# esp-energy-monitor-v2.net
KiCad netlist of a schematic drawn in EAGLE
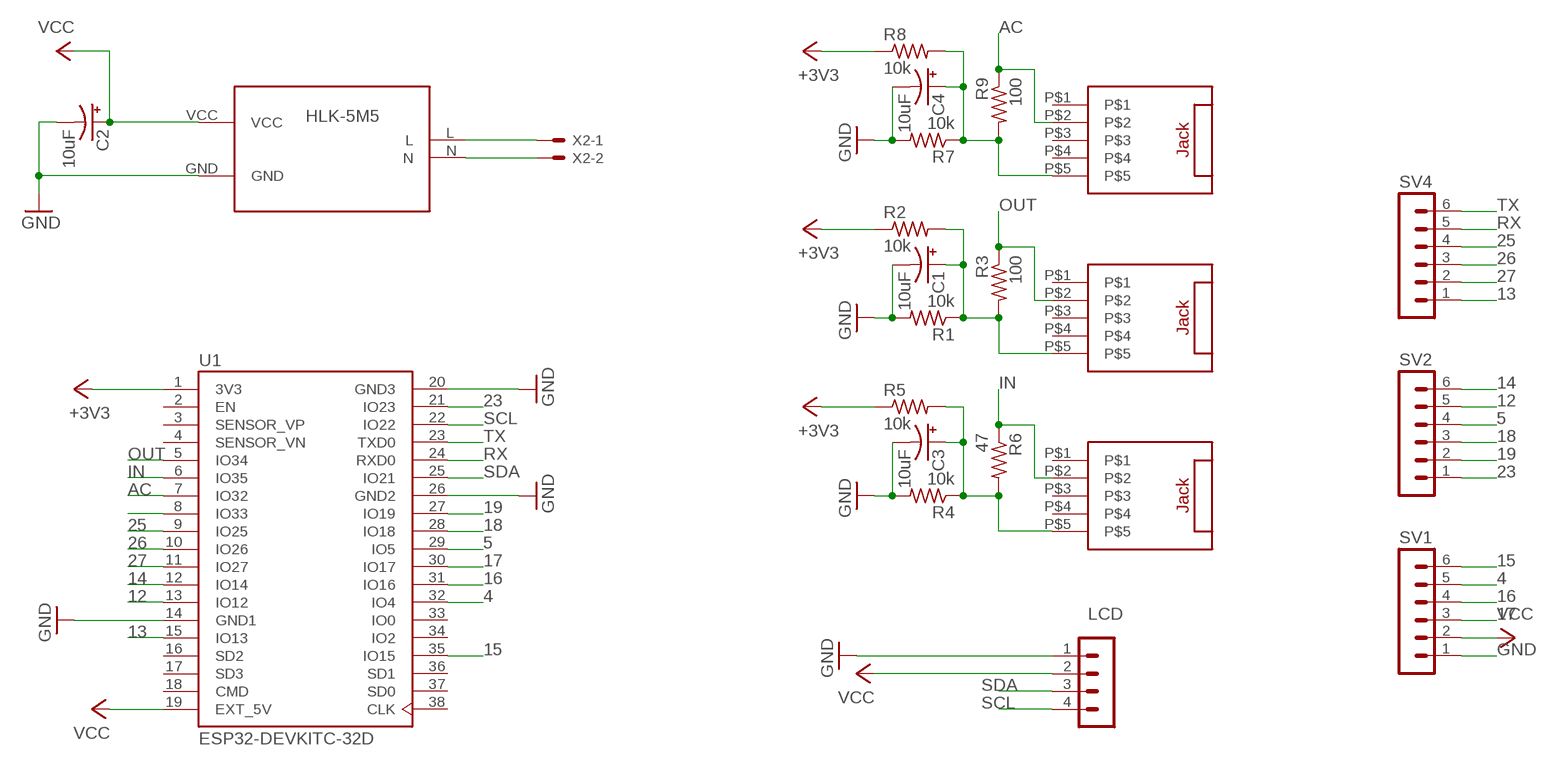
[diagram p0: schematic, sheet 1]

(export (version "E")
  (design (tool "Eeschema 10.0.6"))
  (components
    (comp (ref "ACJACK")
      (value "JACK_5PINS")
      (footprint "eagle-import:JACK_5PINS")
      (libsource (lib "eagle-import") (part "JACK_5PINS"))
    )
    (comp (ref "C1")
      (value "10uF")
      (footprint "eagle-import:B45181A")
      (libsource (lib "eagle-import") (part "CPOL-USB45181A"))
    )
    (comp (ref "C2")
      (value "10uF")
      (footprint "eagle-import:B45181A")
      (libsource (lib "eagle-import") (part "CPOL-USB45181A"))
    )
    (comp (ref "C3")
      (value "10uF")
      (footprint "eagle-import:B45181A")
      (libsource (lib "eagle-import") (part "CPOL-USB45181A"))
    )
    (comp (ref "C4")
      (value "10uF")
      (footprint "eagle-import:B45181A")
      (libsource (lib "eagle-import") (part "CPOL-USB45181A"))
    )
    (comp (ref "HLK-5M5")
      (value "HLK-5M05")
      (footprint "eagle-import:CONV_HLK-5M05")
      (libsource (lib "eagle-import") (part "HLK-5M05"))
    )
    (comp (ref "INJACK")
      (value "JACK_5PINS")
      (footprint "eagle-import:JACK_5PINS")
      (libsource (lib "eagle-import") (part "JACK_5PINS"))
    )
    (comp (ref "OUTJACK")
      (value "JACK_5PINS")
      (footprint "eagle-import:JACK_5PINS")
      (libsource (lib "eagle-import") (part "JACK_5PINS"))
    )
    (comp (ref "R1")
      (value "10k")
      (footprint "eagle-import:0204_7")
      (libsource (lib "eagle-import") (part "R-US_0204/7"))
    )
    (comp (ref "R2")
      (value "10k")
      (footprint "eagle-import:0204_7")
      (libsource (lib "eagle-import") (part "R-US_0204/7"))
    )
    (comp (ref "R3")
      (value "100")
      (footprint "eagle-import:0204_7")
      (libsource (lib "eagle-import") (part "R-US_0204/7"))
    )
    (comp (ref "R4")
      (value "10k")
      (footprint "eagle-import:0204_7")
      (libsource (lib "eagle-import") (part "R-US_0204/7"))
    )
    (comp (ref "R5")
      (value "10k")
      (footprint "eagle-import:0204_7")
      (libsource (lib "eagle-import") (part "R-US_0204/7"))
    )
    (comp (ref "R6")
      (value "47")
      (footprint "eagle-import:0204_7")
      (libsource (lib "eagle-import") (part "R-US_0204/7"))
    )
    (comp (ref "R7")
      (value "10k")
      (footprint "eagle-import:0204_7")
      (libsource (lib "eagle-import") (part "R-US_0204/7"))
    )
    (comp (ref "R8")
      (value "10k")
      (footprint "eagle-import:0204_7")
      (libsource (lib "eagle-import") (part "R-US_0204/7"))
    )
    (comp (ref "R9")
      (value "100")
      (footprint "eagle-import:0204_7")
      (libsource (lib "eagle-import") (part "R-US_0204/7"))
    )
    (comp (ref "SV1")
      (value "MA06-1")
      (footprint "eagle-import:MA06-1")
      (libsource (lib "eagle-import") (part "MA06-1"))
    )
    (comp (ref "SV2")
      (value "MA06-1")
      (footprint "eagle-import:MA06-1")
      (libsource (lib "eagle-import") (part "MA06-1"))
    )
    (comp (ref "SV3")
      (value "MA04-1")
      (footprint "eagle-import:MA04-1")
      (libsource (lib "eagle-import") (part "MA04-1"))
    )
    (comp (ref "SV4")
      (value "MA06-1")
      (footprint "eagle-import:MA06-1")
      (libsource (lib "eagle-import") (part "MA06-1"))
    )
    (comp (ref "U1")
      (value "ESP32-DEVKITC-32D")
      (footprint "eagle-import:MODULE_ESP32-DEVKITC-32D")
      (fields (field (name "MF") "Espressif Systems"))
      (libsource (lib "eagle-import") (part "ESP32-DEVKITC-32D"))
    )
    (comp (ref "X2")
      (value "JST-XH-02-PIN-LONG-PAD")
      (footprint "eagle-import:JST-XH-02-PACKAGE-LONG-PAD")
      (libsource (lib "eagle-import") (part "JST-XH-02-PIN-LONG-PAD"))
    )
  )
  (nets
    (net (code "1") (name "+3V3") (class "Default")
      (node (ref "R2") (pin "1") (pinfunction "1_1") (pintype "passive"))
      (node (ref "R5") (pin "1") (pinfunction "1_1") (pintype "passive"))
      (node (ref "R8") (pin "1") (pinfunction "1_1") (pintype "passive"))
      (node (ref "U1") (pin "1") (pinfunction "3V3_1") (pintype "power_in"))
    )
    (net (code "2") (name "/4") (class "Default")
      (node (ref "SV1") (pin "5") (pinfunction "5_5") (pintype "passive"))
      (node (ref "U1") (pin "32") (pinfunction "IO4_32") (pintype "bidirectional"))
    )
    (net (code "3") (name "/5") (class "Default")
      (node (ref "SV2") (pin "4") (pinfunction "4_4") (pintype "passive"))
      (node (ref "U1") (pin "29") (pinfunction "IO5_29") (pintype "bidirectional"))
    )
    (net (code "4") (name "/12") (class "Default")
      (node (ref "SV2") (pin "5") (pinfunction "5_5") (pintype "passive"))
      (node (ref "U1") (pin "13") (pinfunction "IO12_13") (pintype "bidirectional"))
    )
    (net (code "5") (name "/13") (class "Default")
      (node (ref "SV4") (pin "1") (pinfunction "1_1") (pintype "passive"))
      (node (ref "U1") (pin "15") (pinfunction "IO13_15") (pintype "bidirectional"))
    )
    (net (code "6") (name "/14") (class "Default")
      (node (ref "SV2") (pin "6") (pinfunction "6_6") (pintype "passive"))
      (node (ref "U1") (pin "12") (pinfunction "IO14_12") (pintype "bidirectional"))
    )
    (net (code "7") (name "/15") (class "Default")
      (node (ref "SV1") (pin "6") (pinfunction "6_6") (pintype "passive"))
      (node (ref "U1") (pin "35") (pinfunction "IO15_35") (pintype "bidirectional"))
    )
    (net (code "8") (name "/16") (class "Default")
      (node (ref "SV1") (pin "4") (pinfunction "4_4") (pintype "passive"))
      (node (ref "U1") (pin "31") (pinfunction "IO16_31") (pintype "bidirectional"))
    )
    (net (code "9") (name "/17") (class "Default")
      (node (ref "SV1") (pin "3") (pinfunction "3_3") (pintype "passive"))
      (node (ref "U1") (pin "30") (pinfunction "IO17_30") (pintype "bidirectional"))
    )
    (net (code "10") (name "/18") (class "Default")
      (node (ref "SV2") (pin "3") (pinfunction "3_3") (pintype "passive"))
      (node (ref "U1") (pin "28") (pinfunction "IO18_28") (pintype "bidirectional"))
    )
    (net (code "11") (name "/19") (class "Default")
      (node (ref "SV2") (pin "2") (pinfunction "2_2") (pintype "passive"))
      (node (ref "U1") (pin "27") (pinfunction "IO19_27") (pintype "bidirectional"))
    )
    (net (code "12") (name "/23") (class "Default")
      (node (ref "SV2") (pin "1") (pinfunction "1_1") (pintype "passive"))
      (node (ref "U1") (pin "21") (pinfunction "IO23_21") (pintype "bidirectional"))
    )
    (net (code "13") (name "/25") (class "Default")
      (node (ref "SV4") (pin "4") (pinfunction "4_4") (pintype "passive"))
      (node (ref "U1") (pin "9") (pinfunction "IO25_9") (pintype "bidirectional"))
    )
    (net (code "14") (name "/26") (class "Default")
      (node (ref "SV4") (pin "3") (pinfunction "3_3") (pintype "passive"))
      (node (ref "U1") (pin "10") (pinfunction "IO26_10") (pintype "bidirectional"))
    )
    (net (code "15") (name "/27") (class "Default")
      (node (ref "SV4") (pin "2") (pinfunction "2_2") (pintype "passive"))
      (node (ref "U1") (pin "11") (pinfunction "IO27_11") (pintype "bidirectional"))
    )
    (net (code "16") (name "/AC") (class "Default")
      (node (ref "ACJACK") (pin "P$2") (pinfunction "P$2_P$2") (pintype "bidirectional"))
      (node (ref "R9") (pin "1") (pinfunction "1_1") (pintype "passive"))
      (node (ref "U1") (pin "7") (pinfunction "IO32_7") (pintype "bidirectional"))
    )
    (net (code "17") (name "/IN") (class "Default")
      (node (ref "INJACK") (pin "P$2") (pinfunction "P$2_P$2") (pintype "bidirectional"))
      (node (ref "R6") (pin "1") (pinfunction "1_1") (pintype "passive"))
      (node (ref "U1") (pin "6") (pinfunction "IO35_6") (pintype "bidirectional"))
    )
    (net (code "18") (name "/OUT") (class "Default")
      (node (ref "OUTJACK") (pin "P$2") (pinfunction "P$2_P$2") (pintype "bidirectional"))
      (node (ref "R3") (pin "1") (pinfunction "1_1") (pintype "passive"))
      (node (ref "U1") (pin "5") (pinfunction "IO34_5") (pintype "bidirectional"))
    )
    (net (code "19") (name "/RX") (class "Default")
      (node (ref "SV4") (pin "5") (pinfunction "5_5") (pintype "passive"))
      (node (ref "U1") (pin "24") (pinfunction "RXD0_24") (pintype "input"))
    )
    (net (code "20") (name "/SCL") (class "Default")
      (node (ref "SV3") (pin "4") (pinfunction "4_4") (pintype "passive"))
      (node (ref "U1") (pin "22") (pinfunction "IO22_22") (pintype "bidirectional"))
    )
    (net (code "21") (name "/SDA") (class "Default")
      (node (ref "SV3") (pin "3") (pinfunction "3_3") (pintype "passive"))
      (node (ref "U1") (pin "25") (pinfunction "IO21_25") (pintype "bidirectional"))
    )
    (net (code "22") (name "/TX") (class "Default")
      (node (ref "SV4") (pin "6") (pinfunction "6_6") (pintype "passive"))
      (node (ref "U1") (pin "23") (pinfunction "TXD0_23") (pintype "output"))
    )
    (net (code "23") (name "GND") (class "Default")
      (node (ref "C1") (pin "-") (pinfunction "-_-") (pintype "passive"))
      (node (ref "C2") (pin "-") (pinfunction "-_-") (pintype "passive"))
      (node (ref "C3") (pin "-") (pinfunction "-_-") (pintype "passive"))
      (node (ref "C4") (pin "-") (pinfunction "-_-") (pintype "passive"))
      (node (ref "HLK-5M5") (pin "GND") (pinfunction "GND_GND") (pintype "bidirectional"))
      (node (ref "R1") (pin "2") (pinfunction "2_2") (pintype "passive"))
      (node (ref "R4") (pin "2") (pinfunction "2_2") (pintype "passive"))
      (node (ref "R7") (pin "2") (pinfunction "2_2") (pintype "passive"))
      (node (ref "SV1") (pin "1") (pinfunction "1_1") (pintype "passive"))
      (node (ref "SV3") (pin "1") (pinfunction "1_1") (pintype "passive"))
      (node (ref "U1") (pin "14") (pinfunction "GND1_14") (pintype "power_in"))
      (node (ref "U1") (pin "20") (pinfunction "GND3_20") (pintype "power_in"))
      (node (ref "U1") (pin "26") (pinfunction "GND2_26") (pintype "power_in"))
    )
    (net (code "24") (name "Net-(ACJACK-PadP$5)") (class "Default")
      (node (ref "ACJACK") (pin "P$5") (pinfunction "P$5_P$5") (pintype "bidirectional"))
      (node (ref "C4") (pin "+") (pinfunction "+_+") (pintype "passive"))
      (node (ref "R7") (pin "1") (pinfunction "1_1") (pintype "passive"))
      (node (ref "R8") (pin "2") (pinfunction "2_2") (pintype "passive"))
      (node (ref "R9") (pin "2") (pinfunction "2_2") (pintype "passive"))
    )
    (net (code "25") (name "Net-(C1-Pad+)") (class "Default")
      (node (ref "C1") (pin "+") (pinfunction "+_+") (pintype "passive"))
      (node (ref "OUTJACK") (pin "P$5") (pinfunction "P$5_P$5") (pintype "bidirectional"))
      (node (ref "R1") (pin "1") (pinfunction "1_1") (pintype "passive"))
      (node (ref "R2") (pin "2") (pinfunction "2_2") (pintype "passive"))
      (node (ref "R3") (pin "2") (pinfunction "2_2") (pintype "passive"))
    )
    (net (code "26") (name "Net-(C3-Pad+)") (class "Default")
      (node (ref "C3") (pin "+") (pinfunction "+_+") (pintype "passive"))
      (node (ref "INJACK") (pin "P$5") (pinfunction "P$5_P$5") (pintype "bidirectional"))
      (node (ref "R4") (pin "1") (pinfunction "1_1") (pintype "passive"))
      (node (ref "R5") (pin "2") (pinfunction "2_2") (pintype "passive"))
      (node (ref "R6") (pin "2") (pinfunction "2_2") (pintype "passive"))
    )
    (net (code "27") (name "Net-(X2A-S)") (class "Default")
      (node (ref "HLK-5M5") (pin "L") (pinfunction "L_L") (pintype "bidirectional"))
      (node (ref "X2") (pin "1") (pinfunction "S_1") (pintype "passive"))
    )
    (net (code "28") (name "Net-(X2B-S)") (class "Default")
      (node (ref "HLK-5M5") (pin "N") (pinfunction "N_N") (pintype "bidirectional"))
      (node (ref "X2") (pin "2") (pinfunction "S_2") (pintype "passive"))
    )
    (net (code "29") (name "VCC") (class "Default")
      (node (ref "C2") (pin "+") (pinfunction "+_+") (pintype "passive"))
      (node (ref "HLK-5M5") (pin "VCC") (pinfunction "VCC_VCC") (pintype "bidirectional"))
      (node (ref "SV1") (pin "2") (pinfunction "2_2") (pintype "passive"))
      (node (ref "SV3") (pin "2") (pinfunction "2_2") (pintype "passive"))
      (node (ref "U1") (pin "19") (pinfunction "EXT_5V_19") (pintype "power_in"))
    )
    (net (code "30") (name "unconnected-(ACJACK-PadP$1)") (class "Default")
      (node (ref "ACJACK") (pin "P$1") (pinfunction "P$1_P$1") (pintype "bidirectional"))
    )
    (net (code "31") (name "unconnected-(ACJACK-PadP$3)") (class "Default")
      (node (ref "ACJACK") (pin "P$3") (pinfunction "P$3_P$3") (pintype "bidirectional"))
    )
    (net (code "32") (name "unconnected-(ACJACK-PadP$4)") (class "Default")
      (node (ref "ACJACK") (pin "P$4") (pinfunction "P$4_P$4") (pintype "bidirectional"))
    )
    (net (code "33") (name "unconnected-(INJACK-PadP$1)") (class "Default")
      (node (ref "INJACK") (pin "P$1") (pinfunction "P$1_P$1") (pintype "bidirectional"))
    )
    (net (code "34") (name "unconnected-(INJACK-PadP$3)") (class "Default")
      (node (ref "INJACK") (pin "P$3") (pinfunction "P$3_P$3") (pintype "bidirectional"))
    )
    (net (code "35") (name "unconnected-(INJACK-PadP$4)") (class "Default")
      (node (ref "INJACK") (pin "P$4") (pinfunction "P$4_P$4") (pintype "bidirectional"))
    )
    (net (code "36") (name "unconnected-(OUTJACK-PadP$1)") (class "Default")
      (node (ref "OUTJACK") (pin "P$1") (pinfunction "P$1_P$1") (pintype "bidirectional"))
    )
    (net (code "37") (name "unconnected-(OUTJACK-PadP$3)") (class "Default")
      (node (ref "OUTJACK") (pin "P$3") (pinfunction "P$3_P$3") (pintype "bidirectional"))
    )
    (net (code "38") (name "unconnected-(OUTJACK-PadP$4)") (class "Default")
      (node (ref "OUTJACK") (pin "P$4") (pinfunction "P$4_P$4") (pintype "bidirectional"))
    )
    (net (code "39") (name "unconnected-(U1-CLK-Pad38)") (class "Default")
      (node (ref "U1") (pin "38") (pinfunction "CLK_38") (pintype "input"))
    )
    (net (code "40") (name "unconnected-(U1-CMD-Pad18)") (class "Default")
      (node (ref "U1") (pin "18") (pinfunction "CMD_18") (pintype "bidirectional"))
    )
    (net (code "41") (name "unconnected-(U1-EN-Pad2)") (class "Default")
      (node (ref "U1") (pin "2") (pinfunction "EN_2") (pintype "input"))
    )
    (net (code "42") (name "unconnected-(U1-IO0-Pad33)") (class "Default")
      (node (ref "U1") (pin "33") (pinfunction "IO0_33") (pintype "bidirectional"))
    )
    (net (code "43") (name "unconnected-(U1-IO2-Pad34)") (class "Default")
      (node (ref "U1") (pin "34") (pinfunction "IO2_34") (pintype "bidirectional"))
    )
    (net (code "44") (name "unconnected-(U1-IO33-Pad8)") (class "Default")
      (node (ref "U1") (pin "8") (pinfunction "IO33_8") (pintype "bidirectional"))
    )
    (net (code "45") (name "unconnected-(U1-SD0-Pad37)") (class "Default")
      (node (ref "U1") (pin "37") (pinfunction "SD0_37") (pintype "bidirectional"))
    )
    (net (code "46") (name "unconnected-(U1-SD1-Pad36)") (class "Default")
      (node (ref "U1") (pin "36") (pinfunction "SD1_36") (pintype "bidirectional"))
    )
    (net (code "47") (name "unconnected-(U1-SD2-Pad16)") (class "Default")
      (node (ref "U1") (pin "16") (pinfunction "SD2_16") (pintype "bidirectional"))
    )
    (net (code "48") (name "unconnected-(U1-SD3-Pad17)") (class "Default")
      (node (ref "U1") (pin "17") (pinfunction "SD3_17") (pintype "bidirectional"))
    )
    (net (code "49") (name "unconnected-(U1-SENSOR_VN-Pad4)") (class "Default")
      (node (ref "U1") (pin "4") (pinfunction "SENSOR_VN_4") (pintype "input"))
    )
    (net (code "50") (name "unconnected-(U1-SENSOR_VP-Pad3)") (class "Default")
      (node (ref "U1") (pin "3") (pinfunction "SENSOR_VP_3") (pintype "input"))
    )
  )
)
